# unonano.net
KiCad netlist of a schematic drawn in EAGLE
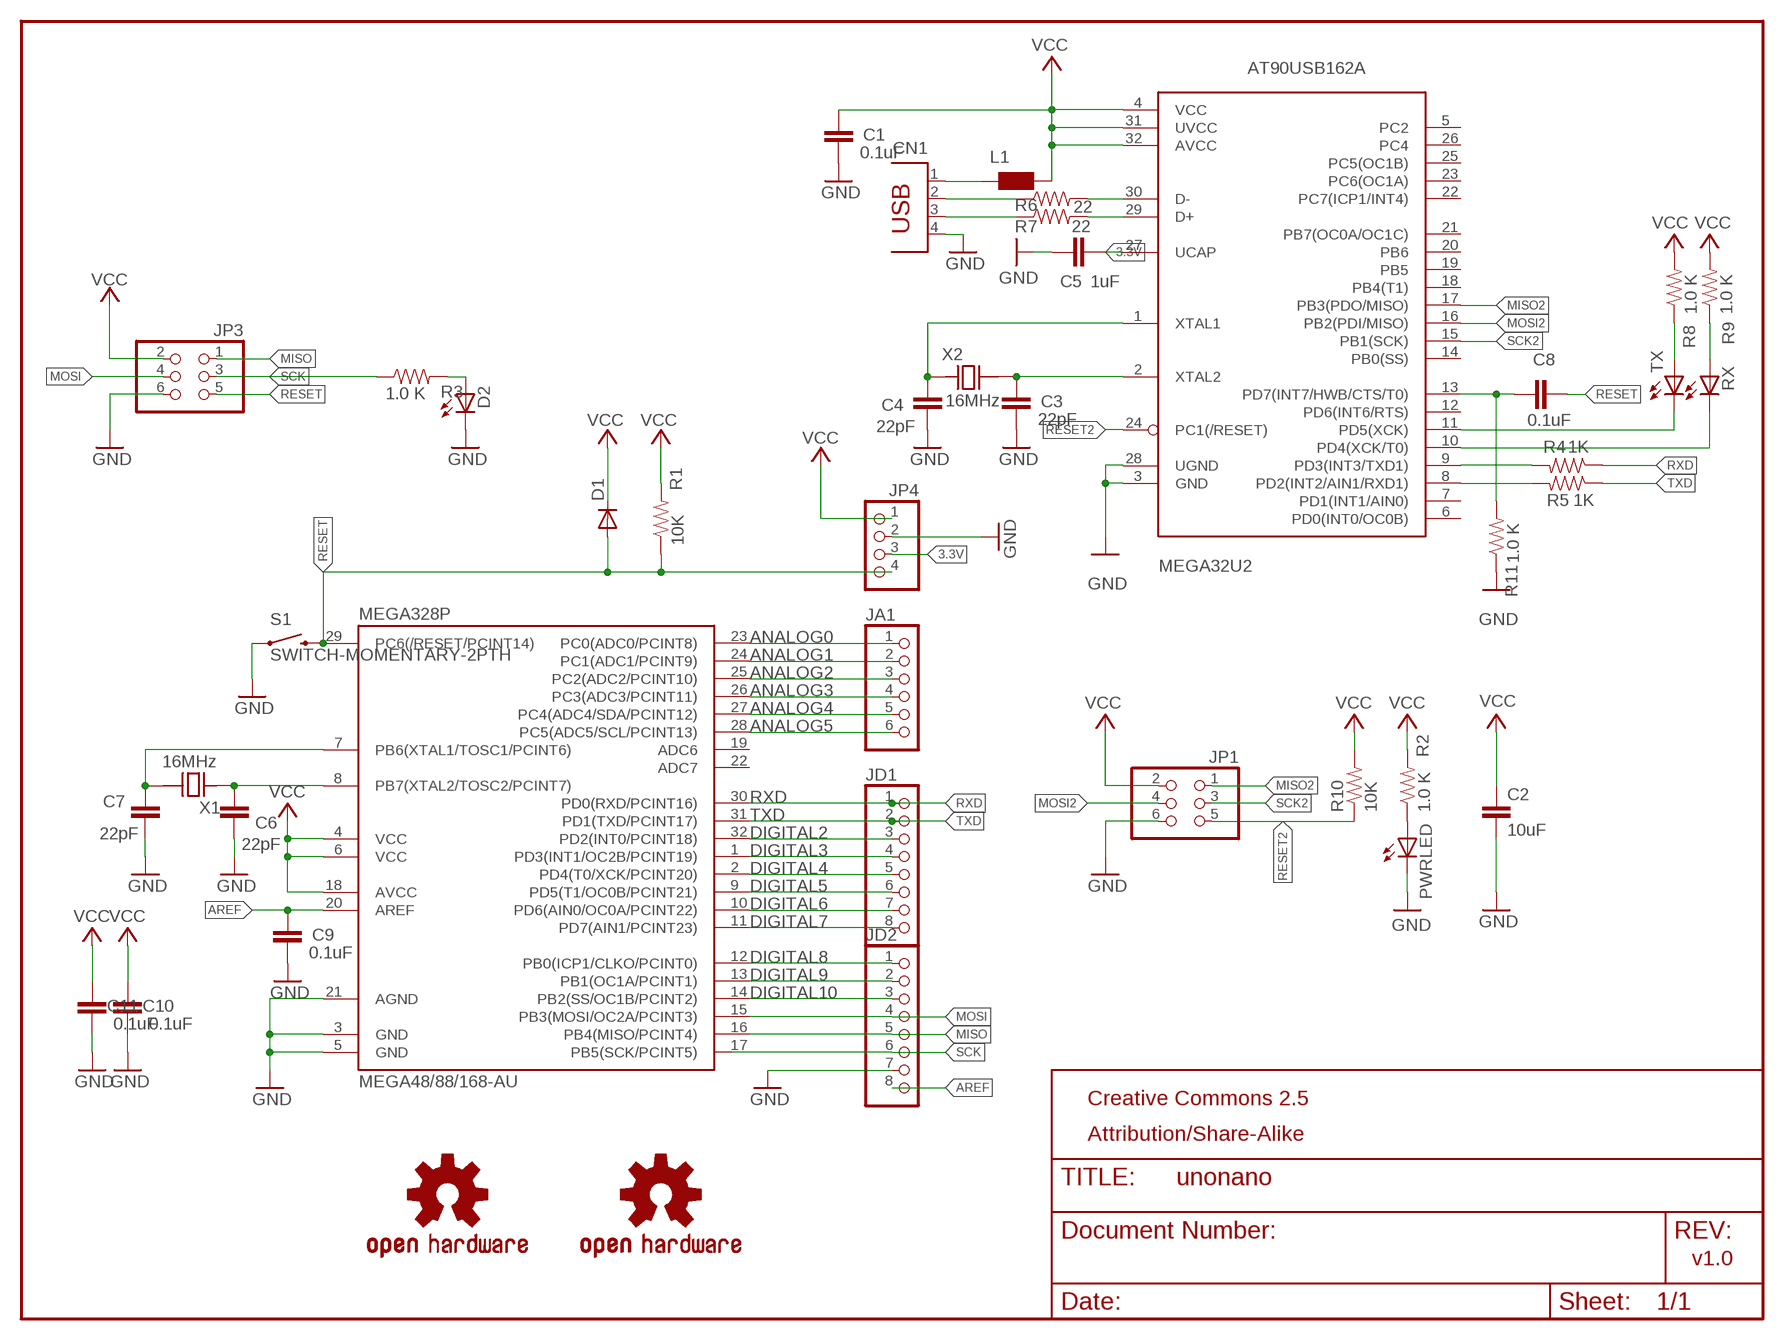
[diagram p0: schematic, sheet 1]

(export (version "E")
  (design (tool "Eeschema 10.0.6"))
  (components
    (comp (ref "C1")
      (value "0.1uF")
      (footprint "eagle-import:0805")
      (libsource (lib "eagle-import") (part "CAP0805"))
    )
    (comp (ref "C2")
      (value "10uF")
      (footprint "eagle-import:1206")
      (libsource (lib "eagle-import") (part "1.0UF50V10%(1206)"))
    )
    (comp (ref "C3")
      (value "22pF")
      (footprint "eagle-import:0805")
      (libsource (lib "eagle-import") (part "CAP0805"))
    )
    (comp (ref "C4")
      (value "22pF")
      (footprint "eagle-import:0805")
      (libsource (lib "eagle-import") (part "CAP0805"))
    )
    (comp (ref "C5")
      (value "1uF")
      (footprint "eagle-import:0805")
      (libsource (lib "eagle-import") (part "CAP0805"))
    )
    (comp (ref "C6")
      (value "22pF")
      (footprint "eagle-import:0805")
      (libsource (lib "eagle-import") (part "CAP0805"))
    )
    (comp (ref "C7")
      (value "22pF")
      (footprint "eagle-import:0805")
      (libsource (lib "eagle-import") (part "CAP0805"))
    )
    (comp (ref "C8")
      (value "0.1uF")
      (footprint "eagle-import:0805")
      (libsource (lib "eagle-import") (part "CAP0805"))
    )
    (comp (ref "C9")
      (value "0.1uF")
      (footprint "eagle-import:0805")
      (libsource (lib "eagle-import") (part "CAP0805"))
    )
    (comp (ref "C10")
      (value "0.1uF")
      (footprint "eagle-import:0805")
      (libsource (lib "eagle-import") (part "CAP0805"))
    )
    (comp (ref "C11")
      (value "0.1uF")
      (footprint "eagle-import:0805")
      (libsource (lib "eagle-import") (part "CAP0805"))
    )
    (comp (ref "CN1")
      (value "PN61729")
      (footprint "eagle-import:PN61729")
      (libsource (lib "eagle-import") (part "PN61729"))
    )
    (comp (ref "D1")
      (value "DIODESOD")
      (footprint "eagle-import:SOD-323")
      (libsource (lib "eagle-import") (part "DIODESOD"))
    )
    (comp (ref "D2")
      (value "Green")
      (footprint "eagle-import:CHIP-LED0805")
      (libsource (lib "eagle-import") (part "LEDCHIP-LED0805"))
    )
    (comp (ref "JA1")
      (value "PINHD-1X6CB")
      (footprint "eagle-import:1X06-CLEANBIG")
      (libsource (lib "eagle-import") (part "PINHD-1X6CB"))
    )
    (comp (ref "JD1")
      (value "PINHD-1X8CLEANBIG")
      (footprint "eagle-import:1X08-CLEANBIG")
      (libsource (lib "eagle-import") (part "PINHD-1X8CLEANBIG"))
    )
    (comp (ref "JD2")
      (value "PINHD-1X8CLEANBIG")
      (footprint "eagle-import:1X08-CLEANBIG")
      (libsource (lib "eagle-import") (part "PINHD-1X8CLEANBIG"))
    )
    (comp (ref "JP1")
      (value "PINHD-2X3")
      (footprint "eagle-import:2X03")
      (libsource (lib "eagle-import") (part "PINHD-2X3"))
    )
    (comp (ref "JP3")
      (value "PINHD-2X3")
      (footprint "eagle-import:2X03")
      (libsource (lib "eagle-import") (part "PINHD-2X3"))
    )
    (comp (ref "JP4")
      (value "PINHD-1X4CB")
      (footprint "eagle-import:1X04-CB")
      (libsource (lib "eagle-import") (part "PINHD-1X4CB"))
    )
    (comp (ref "L1")
      (value "WE-CBF")
      (footprint "eagle-import:1812")
      (libsource (lib "eagle-import") (part "WE-CBF"))
    )
    (comp (ref "LOGO1")
      (value "OSHW-LOGOL")
      (footprint "eagle-import:OSHW-LOGO-L")
      (libsource (lib "eagle-import") (part "OSHW-LOGOL"))
    )
    (comp (ref "LOGO2")
      (value "OSHW-LOGOS")
      (footprint "eagle-import:OSHW-LOGO-S")
      (libsource (lib "eagle-import") (part "OSHW-LOGOS"))
    )
    (comp (ref "MEGA32U2")
      (value "AT90USB162A")
      (footprint "eagle-import:TQFP32-08")
      (libsource (lib "eagle-import") (part "AT90USB162A"))
    )
    (comp (ref "MEGA328P")
      (value "MEGA48/88/168-AU")
      (footprint "eagle-import:TQFP32-08")
      (libsource (lib "eagle-import") (part "MEGA48/88/168-AU"))
    )
    (comp (ref "PWRLED")
      (value "LEDCHIP-LED0805")
      (footprint "eagle-import:CHIP-LED0805")
      (libsource (lib "eagle-import") (part "LEDCHIP-LED0805"))
    )
    (comp (ref "R1")
      (value "10K")
      (footprint "eagle-import:0805")
      (libsource (lib "eagle-import") (part "RESISTOR0805-RES"))
    )
    (comp (ref "R2")
      (value "1.0 K")
      (footprint "eagle-import:0805")
      (libsource (lib "eagle-import") (part "RESISTOR0805-RES"))
    )
    (comp (ref "R3")
      (value "1.0 K")
      (footprint "eagle-import:0805")
      (libsource (lib "eagle-import") (part "RESISTOR0805-RES"))
    )
    (comp (ref "R4")
      (value "1K")
      (footprint "eagle-import:0805")
      (libsource (lib "eagle-import") (part "RESISTOR0805-RES"))
    )
    (comp (ref "R5")
      (value "1K")
      (footprint "eagle-import:0805")
      (libsource (lib "eagle-import") (part "RESISTOR0805-RES"))
    )
    (comp (ref "R6")
      (value "22")
      (footprint "eagle-import:0805")
      (libsource (lib "eagle-import") (part "RESISTOR0805-RES"))
    )
    (comp (ref "R7")
      (value "22")
      (footprint "eagle-import:0805")
      (libsource (lib "eagle-import") (part "RESISTOR0805-RES"))
    )
    (comp (ref "R8")
      (value "1.0 K")
      (footprint "eagle-import:0805")
      (libsource (lib "eagle-import") (part "RESISTOR0805-RES"))
    )
    (comp (ref "R9")
      (value "1.0 K")
      (footprint "eagle-import:0805")
      (libsource (lib "eagle-import") (part "RESISTOR0805-RES"))
    )
    (comp (ref "R10")
      (value "10K")
      (footprint "eagle-import:0805")
      (libsource (lib "eagle-import") (part "RESISTOR0805-RES"))
    )
    (comp (ref "R11")
      (value "1.0 K")
      (footprint "eagle-import:0805")
      (libsource (lib "eagle-import") (part "RESISTOR0805-RES"))
    )
    (comp (ref "RX")
      (value "Green")
      (footprint "eagle-import:CHIP-LED0805")
      (libsource (lib "eagle-import") (part "LEDCHIP-LED0805"))
    )
    (comp (ref "S1")
      (value "SWITCH-MOMENTARY-2PTH")
      (footprint "eagle-import:TACTILE-PTH")
      (libsource (lib "eagle-import") (part "SWITCH-MOMENTARY-2PTH"))
    )
    (comp (ref "TX")
      (value "Green")
      (footprint "eagle-import:CHIP-LED0805")
      (libsource (lib "eagle-import") (part "LEDCHIP-LED0805"))
    )
    (comp (ref "X1")
      (value "16MHz")
      (footprint "eagle-import:FA238")
      (libsource (lib "eagle-import") (part "CRYSTALFA238"))
    )
    (comp (ref "X2")
      (value "16MHz")
      (footprint "eagle-import:FA238")
      (libsource (lib "eagle-import") (part "CRYSTALFA238"))
    )
  )
  (nets
    (net (code "1") (name "/ANALOG0") (class "Default")
      (node (ref "JA1") (pin "1") (pinfunction "1_1") (pintype "passive"))
      (node (ref "MEGA328P") (pin "23") (pinfunction "PC0(ADC0/PCINT8)_23") (pintype "bidirectional"))
    )
    (net (code "2") (name "/ANALOG1") (class "Default")
      (node (ref "JA1") (pin "2") (pinfunction "2_2") (pintype "passive"))
      (node (ref "MEGA328P") (pin "24") (pinfunction "PC1(ADC1/PCINT9)_24") (pintype "bidirectional"))
    )
    (net (code "3") (name "/ANALOG2") (class "Default")
      (node (ref "JA1") (pin "3") (pinfunction "3_3") (pintype "passive"))
      (node (ref "MEGA328P") (pin "25") (pinfunction "PC2(ADC2/PCINT10)_25") (pintype "bidirectional"))
    )
    (net (code "4") (name "/ANALOG3") (class "Default")
      (node (ref "JA1") (pin "4") (pinfunction "4_4") (pintype "passive"))
      (node (ref "MEGA328P") (pin "26") (pinfunction "PC3(ADC3/PCINT11)_26") (pintype "bidirectional"))
    )
    (net (code "5") (name "/ANALOG4") (class "Default")
      (node (ref "JA1") (pin "5") (pinfunction "5_5") (pintype "passive"))
      (node (ref "MEGA328P") (pin "27") (pinfunction "PC4(ADC4/SDA/PCINT12)_27") (pintype "bidirectional"))
    )
    (net (code "6") (name "/ANALOG5") (class "Default")
      (node (ref "JA1") (pin "6") (pinfunction "6_6") (pintype "passive"))
      (node (ref "MEGA328P") (pin "28") (pinfunction "PC5(ADC5/SCL/PCINT13)_28") (pintype "bidirectional"))
    )
    (net (code "7") (name "/DIGITAL2") (class "Default")
      (node (ref "JD1") (pin "3") (pinfunction "3_3") (pintype "passive"))
      (node (ref "MEGA328P") (pin "32") (pinfunction "PD2(INT0/PCINT18)_32") (pintype "bidirectional"))
    )
    (net (code "8") (name "/DIGITAL3") (class "Default")
      (node (ref "JD1") (pin "4") (pinfunction "4_4") (pintype "passive"))
      (node (ref "MEGA328P") (pin "1") (pinfunction "PD3(INT1/OC2B/PCINT19)_1") (pintype "bidirectional"))
    )
    (net (code "9") (name "/DIGITAL4") (class "Default")
      (node (ref "JD1") (pin "5") (pinfunction "5_5") (pintype "passive"))
      (node (ref "MEGA328P") (pin "2") (pinfunction "PD4(T0/XCK/PCINT20)_2") (pintype "bidirectional"))
    )
    (net (code "10") (name "/DIGITAL5") (class "Default")
      (node (ref "JD1") (pin "6") (pinfunction "6_6") (pintype "passive"))
      (node (ref "MEGA328P") (pin "9") (pinfunction "PD5(T1/OC0B/PCINT21)_9") (pintype "bidirectional"))
    )
    (net (code "11") (name "/DIGITAL6") (class "Default")
      (node (ref "JD1") (pin "7") (pinfunction "7_7") (pintype "passive"))
      (node (ref "MEGA328P") (pin "10") (pinfunction "PD6(AIN0/OC0A/PCINT22)_10") (pintype "bidirectional"))
    )
    (net (code "12") (name "/DIGITAL7") (class "Default")
      (node (ref "JD1") (pin "8") (pinfunction "8_8") (pintype "passive"))
      (node (ref "MEGA328P") (pin "11") (pinfunction "PD7(AIN1/PCINT23)_11") (pintype "bidirectional"))
    )
    (net (code "13") (name "/DIGITAL8") (class "Default")
      (node (ref "JD2") (pin "1") (pinfunction "1_1") (pintype "passive"))
      (node (ref "MEGA328P") (pin "12") (pinfunction "PB0(ICP1/CLKO/PCINT0)_12") (pintype "bidirectional"))
    )
    (net (code "14") (name "/DIGITAL9") (class "Default")
      (node (ref "JD2") (pin "2") (pinfunction "2_2") (pintype "passive"))
      (node (ref "MEGA328P") (pin "13") (pinfunction "PB1(OC1A/PCINT1)_13") (pintype "bidirectional"))
    )
    (net (code "15") (name "/DIGITAL10") (class "Default")
      (node (ref "JD2") (pin "3") (pinfunction "3_3") (pintype "passive"))
      (node (ref "MEGA328P") (pin "14") (pinfunction "PB2(SS/OC1B/PCINT2)_14") (pintype "bidirectional"))
    )
    (net (code "16") (name "3.3V") (class "Default")
      (node (ref "C5") (pin "1") (pinfunction "1_1") (pintype "passive"))
      (node (ref "JP4") (pin "3") (pinfunction "3_3") (pintype "passive"))
      (node (ref "MEGA32U2") (pin "27") (pinfunction "UCAP_27") (pintype "bidirectional"))
    )
    (net (code "17") (name "AREF") (class "Default")
      (node (ref "C9") (pin "1") (pinfunction "1_1") (pintype "passive"))
      (node (ref "JD2") (pin "8") (pinfunction "8_8") (pintype "passive"))
      (node (ref "MEGA328P") (pin "20") (pinfunction "AREF_20") (pintype "passive"))
    )
    (net (code "18") (name "GND") (class "Default")
      (node (ref "C1") (pin "2") (pinfunction "2_2") (pintype "passive"))
      (node (ref "C10") (pin "2") (pinfunction "2_2") (pintype "passive"))
      (node (ref "C11") (pin "2") (pinfunction "2_2") (pintype "passive"))
      (node (ref "C2") (pin "2") (pinfunction "2_2") (pintype "passive"))
      (node (ref "C3") (pin "2") (pinfunction "2_2") (pintype "passive"))
      (node (ref "C4") (pin "1") (pinfunction "1_1") (pintype "passive"))
      (node (ref "C5") (pin "2") (pinfunction "2_2") (pintype "passive"))
      (node (ref "C6") (pin "2") (pinfunction "2_2") (pintype "passive"))
      (node (ref "C7") (pin "1") (pinfunction "1_1") (pintype "passive"))
      (node (ref "C9") (pin "2") (pinfunction "2_2") (pintype "passive"))
      (node (ref "CN1") (pin "4") (pinfunction "4_4") (pintype "bidirectional"))
      (node (ref "D2") (pin "C") (pinfunction "C_C") (pintype "passive"))
      (node (ref "JD2") (pin "7") (pinfunction "7_7") (pintype "passive"))
      (node (ref "JP1") (pin "6") (pinfunction "6_6") (pintype "passive"))
      (node (ref "JP3") (pin "6") (pinfunction "6_6") (pintype "passive"))
      (node (ref "JP4") (pin "2") (pinfunction "2_2") (pintype "passive"))
      (node (ref "MEGA328P") (pin "21") (pinfunction "AGND_21") (pintype "power_in"))
      (node (ref "MEGA328P") (pin "3") (pinfunction "GND_3") (pintype "power_in"))
      (node (ref "MEGA328P") (pin "5") (pinfunction "GND_5") (pintype "power_in"))
      (node (ref "MEGA32U2") (pin "28") (pinfunction "UGND_28") (pintype "bidirectional"))
      (node (ref "MEGA32U2") (pin "3") (pinfunction "GND_3") (pintype "bidirectional"))
      (node (ref "PWRLED") (pin "C") (pinfunction "C_C") (pintype "passive"))
      (node (ref "R11") (pin "1") (pinfunction "1_1") (pintype "passive"))
      (node (ref "S1") (pin "1") (pinfunction "1_1") (pintype "passive"))
    )
    (net (code "19") (name "MISO") (class "Default")
      (node (ref "JD2") (pin "5") (pinfunction "5_5") (pintype "passive"))
      (node (ref "JP3") (pin "1") (pinfunction "1_1") (pintype "passive"))
      (node (ref "MEGA328P") (pin "16") (pinfunction "PB4(MISO/PCINT4)_16") (pintype "bidirectional"))
    )
    (net (code "20") (name "MISO2") (class "Default")
      (node (ref "JP1") (pin "1") (pinfunction "1_1") (pintype "passive"))
      (node (ref "MEGA32U2") (pin "17") (pinfunction "PB3(PDO/MISO)_17") (pintype "bidirectional"))
    )
    (net (code "21") (name "MOSI") (class "Default")
      (node (ref "JD2") (pin "4") (pinfunction "4_4") (pintype "passive"))
      (node (ref "JP3") (pin "4") (pinfunction "4_4") (pintype "passive"))
      (node (ref "MEGA328P") (pin "15") (pinfunction "PB3(MOSI/OC2A/PCINT3)_15") (pintype "bidirectional"))
    )
    (net (code "22") (name "MOSI2") (class "Default")
      (node (ref "JP1") (pin "4") (pinfunction "4_4") (pintype "passive"))
      (node (ref "MEGA32U2") (pin "16") (pinfunction "PB2(PDI/MISO)_16") (pintype "bidirectional"))
    )
    (net (code "23") (name "Net-(CN1-Pad1)") (class "Default")
      (node (ref "CN1") (pin "1") (pinfunction "1_1") (pintype "bidirectional"))
      (node (ref "L1") (pin "1") (pinfunction "1_1") (pintype "passive"))
    )
    (net (code "24") (name "Net-(CN1-Pad2)") (class "Default")
      (node (ref "CN1") (pin "2") (pinfunction "2_2") (pintype "bidirectional"))
      (node (ref "R6") (pin "1") (pinfunction "1_1") (pintype "passive"))
    )
    (net (code "25") (name "Net-(CN1-Pad3)") (class "Default")
      (node (ref "CN1") (pin "3") (pinfunction "3_3") (pintype "bidirectional"))
      (node (ref "R7") (pin "1") (pinfunction "1_1") (pintype "passive"))
    )
    (net (code "26") (name "Net-(D2-PadA)") (class "Default")
      (node (ref "D2") (pin "A") (pinfunction "A_A") (pintype "passive"))
      (node (ref "R3") (pin "2") (pinfunction "2_2") (pintype "passive"))
    )
    (net (code "27") (name "Net-(MEGA32U2-D+)") (class "Default")
      (node (ref "MEGA32U2") (pin "29") (pinfunction "D+_29") (pintype "bidirectional"))
      (node (ref "R7") (pin "2") (pinfunction "2_2") (pintype "passive"))
    )
    (net (code "28") (name "Net-(MEGA32U2-D-)") (class "Default")
      (node (ref "MEGA32U2") (pin "30") (pinfunction "D-_30") (pintype "bidirectional"))
      (node (ref "R6") (pin "2") (pinfunction "2_2") (pintype "passive"))
    )
    (net (code "29") (name "Net-(MEGA32U2-PD2(INT2{slash}AIN1{slash}RXD1))") (class "Default")
      (node (ref "MEGA32U2") (pin "8") (pinfunction "PD2(INT2/AIN1/RXD1)_8") (pintype "bidirectional"))
      (node (ref "R5") (pin "2") (pinfunction "2_2") (pintype "passive"))
    )
    (net (code "30") (name "Net-(MEGA32U2-PD3(INT3{slash}TXD1))") (class "Default")
      (node (ref "MEGA32U2") (pin "9") (pinfunction "PD3(INT3/TXD1)_9") (pintype "bidirectional"))
      (node (ref "R4") (pin "2") (pinfunction "2_2") (pintype "passive"))
    )
    (net (code "31") (name "Net-(MEGA32U2-PD4(XCK{slash}T0))") (class "Default")
      (node (ref "MEGA32U2") (pin "10") (pinfunction "PD4(XCK/T0)_10") (pintype "bidirectional"))
      (node (ref "RX") (pin "C") (pinfunction "C_C") (pintype "passive"))
    )
    (net (code "32") (name "Net-(MEGA32U2-PD5(XCK))") (class "Default")
      (node (ref "MEGA32U2") (pin "11") (pinfunction "PD5(XCK)_11") (pintype "bidirectional"))
      (node (ref "TX") (pin "C") (pinfunction "C_C") (pintype "passive"))
    )
    (net (code "33") (name "Net-(MEGA32U2-PD7(INT7{slash}HWB{slash}CTS{slash}T0))") (class "Default")
      (node (ref "C8") (pin "1") (pinfunction "1_1") (pintype "passive"))
      (node (ref "MEGA32U2") (pin "13") (pinfunction "PD7(INT7/HWB/CTS/T0)_13") (pintype "bidirectional"))
      (node (ref "R11") (pin "2") (pinfunction "2_2") (pintype "passive"))
    )
    (net (code "34") (name "Net-(MEGA32U2-XTAL1)") (class "Default")
      (node (ref "C4") (pin "2") (pinfunction "2_2") (pintype "passive"))
      (node (ref "MEGA32U2") (pin "1") (pinfunction "XTAL1_1") (pintype "bidirectional"))
      (node (ref "X2") (pin "1") (pinfunction "0_1") (pintype "passive"))
    )
    (net (code "35") (name "Net-(MEGA32U2-XTAL2)") (class "Default")
      (node (ref "C3") (pin "1") (pinfunction "1_1") (pintype "passive"))
      (node (ref "MEGA32U2") (pin "2") (pinfunction "XTAL2_2") (pintype "bidirectional"))
      (node (ref "X2") (pin "3") (pinfunction "1_3") (pintype "passive"))
    )
    (net (code "36") (name "Net-(MEGA328P-PB6(XTAL1{slash}TOSC1{slash}PCINT6))") (class "Default")
      (node (ref "C7") (pin "2") (pinfunction "2_2") (pintype "passive"))
      (node (ref "MEGA328P") (pin "7") (pinfunction "PB6(XTAL1/TOSC1/PCINT6)_7") (pintype "bidirectional"))
      (node (ref "X1") (pin "3") (pinfunction "1_3") (pintype "passive"))
    )
    (net (code "37") (name "Net-(MEGA328P-PB7(XTAL2{slash}TOSC2{slash}PCINT7))") (class "Default")
      (node (ref "C6") (pin "1") (pinfunction "1_1") (pintype "passive"))
      (node (ref "MEGA328P") (pin "8") (pinfunction "PB7(XTAL2/TOSC2/PCINT7)_8") (pintype "bidirectional"))
      (node (ref "X1") (pin "1") (pinfunction "0_1") (pintype "passive"))
    )
    (net (code "38") (name "Net-(PWRLED-PadA)") (class "Default")
      (node (ref "PWRLED") (pin "A") (pinfunction "A_A") (pintype "passive"))
      (node (ref "R2") (pin "1") (pinfunction "1_1") (pintype "passive"))
    )
    (net (code "39") (name "Net-(R8-Pad1)") (class "Default")
      (node (ref "R8") (pin "1") (pinfunction "1_1") (pintype "passive"))
      (node (ref "TX") (pin "A") (pinfunction "A_A") (pintype "passive"))
    )
    (net (code "40") (name "Net-(R9-Pad1)") (class "Default")
      (node (ref "R9") (pin "1") (pinfunction "1_1") (pintype "passive"))
      (node (ref "RX") (pin "A") (pinfunction "A_A") (pintype "passive"))
    )
    (net (code "41") (name "RESET") (class "Default")
      (node (ref "C8") (pin "2") (pinfunction "2_2") (pintype "passive"))
      (node (ref "D1") (pin "2") (pinfunction "A_2") (pintype "passive"))
      (node (ref "JP3") (pin "5") (pinfunction "5_5") (pintype "passive"))
      (node (ref "JP4") (pin "4") (pinfunction "4_4") (pintype "passive"))
      (node (ref "MEGA328P") (pin "29") (pinfunction "PC6(/RESET/PCINT14)_29") (pintype "bidirectional"))
      (node (ref "R1") (pin "1") (pinfunction "1_1") (pintype "passive"))
      (node (ref "S1") (pin "3") (pinfunction "2_3") (pintype "passive"))
    )
    (net (code "42") (name "RESET2") (class "Default")
      (node (ref "JP1") (pin "5") (pinfunction "5_5") (pintype "passive"))
      (node (ref "MEGA32U2") (pin "24") (pinfunction "PC1(/RESET)_24") (pintype "bidirectional"))
      (node (ref "R10") (pin "1") (pinfunction "1_1") (pintype "passive"))
    )
    (net (code "43") (name "RXD") (class "Default")
      (node (ref "JD1") (pin "1") (pinfunction "1_1") (pintype "passive"))
      (node (ref "MEGA328P") (pin "30") (pinfunction "PD0(RXD/PCINT16)_30") (pintype "bidirectional"))
      (node (ref "R4") (pin "1") (pinfunction "1_1") (pintype "passive"))
    )
    (net (code "44") (name "SCK") (class "Default")
      (node (ref "JD2") (pin "6") (pinfunction "6_6") (pintype "passive"))
      (node (ref "JP3") (pin "3") (pinfunction "3_3") (pintype "passive"))
      (node (ref "MEGA328P") (pin "17") (pinfunction "PB5(SCK/PCINT5)_17") (pintype "bidirectional"))
      (node (ref "R3") (pin "1") (pinfunction "1_1") (pintype "passive"))
    )
    (net (code "45") (name "SCK2") (class "Default")
      (node (ref "JP1") (pin "3") (pinfunction "3_3") (pintype "passive"))
      (node (ref "MEGA32U2") (pin "15") (pinfunction "PB1(SCK)_15") (pintype "bidirectional"))
    )
    (net (code "46") (name "TXD") (class "Default")
      (node (ref "JD1") (pin "2") (pinfunction "2_2") (pintype "passive"))
      (node (ref "MEGA328P") (pin "31") (pinfunction "PD1(TXD/PCINT17)_31") (pintype "bidirectional"))
      (node (ref "R5") (pin "1") (pinfunction "1_1") (pintype "passive"))
    )
    (net (code "47") (name "VCC") (class "Default")
      (node (ref "C1") (pin "1") (pinfunction "1_1") (pintype "passive"))
      (node (ref "C10") (pin "1") (pinfunction "1_1") (pintype "passive"))
      (node (ref "C11") (pin "1") (pinfunction "1_1") (pintype "passive"))
      (node (ref "C2") (pin "1") (pinfunction "1_1") (pintype "passive"))
      (node (ref "D1") (pin "1") (pinfunction "C_1") (pintype "passive"))
      (node (ref "JP1") (pin "2") (pinfunction "2_2") (pintype "passive"))
      (node (ref "JP3") (pin "2") (pinfunction "2_2") (pintype "passive"))
      (node (ref "JP4") (pin "1") (pinfunction "1_1") (pintype "passive"))
      (node (ref "L1") (pin "2") (pinfunction "2_2") (pintype "passive"))
      (node (ref "MEGA328P") (pin "18") (pinfunction "AVCC_18") (pintype "passive"))
      (node (ref "MEGA328P") (pin "4") (pinfunction "VCC_4") (pintype "power_in"))
      (node (ref "MEGA328P") (pin "6") (pinfunction "VCC_6") (pintype "power_in"))
      (node (ref "MEGA32U2") (pin "31") (pinfunction "UVCC_31") (pintype "bidirectional"))
      (node (ref "MEGA32U2") (pin "32") (pinfunction "AVCC_32") (pintype "bidirectional"))
      (node (ref "MEGA32U2") (pin "4") (pinfunction "VCC_4") (pintype "bidirectional"))
      (node (ref "R1") (pin "2") (pinfunction "2_2") (pintype "passive"))
      (node (ref "R10") (pin "2") (pinfunction "2_2") (pintype "passive"))
      (node (ref "R2") (pin "2") (pinfunction "2_2") (pintype "passive"))
      (node (ref "R8") (pin "2") (pinfunction "2_2") (pintype "passive"))
      (node (ref "R9") (pin "2") (pinfunction "2_2") (pintype "passive"))
    )
    (net (code "48") (name "unconnected-(MEGA32U2-PB0(SS)-Pad14)") (class "Default")
      (node (ref "MEGA32U2") (pin "14") (pinfunction "PB0(SS)_14") (pintype "bidirectional"))
    )
    (net (code "49") (name "unconnected-(MEGA32U2-PB4(T1)-Pad18)") (class "Default")
      (node (ref "MEGA32U2") (pin "18") (pinfunction "PB4(T1)_18") (pintype "bidirectional"))
    )
    (net (code "50") (name "unconnected-(MEGA32U2-PB5-Pad19)") (class "Default")
      (node (ref "MEGA32U2") (pin "19") (pinfunction "PB5_19") (pintype "bidirectional"))
    )
    (net (code "51") (name "unconnected-(MEGA32U2-PB6-Pad20)") (class "Default")
      (node (ref "MEGA32U2") (pin "20") (pinfunction "PB6_20") (pintype "bidirectional"))
    )
    (net (code "52") (name "unconnected-(MEGA32U2-PB7(OC0A{slash}OC1C)-Pad21)") (class "Default")
      (node (ref "MEGA32U2") (pin "21") (pinfunction "PB7(OC0A/OC1C)_21") (pintype "bidirectional"))
    )
    (net (code "53") (name "unconnected-(MEGA32U2-PC2-Pad5)") (class "Default")
      (node (ref "MEGA32U2") (pin "5") (pinfunction "PC2_5") (pintype "bidirectional"))
    )
    (net (code "54") (name "unconnected-(MEGA32U2-PC4-Pad26)") (class "Default")
      (node (ref "MEGA32U2") (pin "26") (pinfunction "PC4_26") (pintype "bidirectional"))
    )
    (net (code "55") (name "unconnected-(MEGA32U2-PC5(OC1B)-Pad25)") (class "Default")
      (node (ref "MEGA32U2") (pin "25") (pinfunction "PC5(OC1B)_25") (pintype "bidirectional"))
    )
    (net (code "56") (name "unconnected-(MEGA32U2-PC6(OC1A)-Pad23)") (class "Default")
      (node (ref "MEGA32U2") (pin "23") (pinfunction "PC6(OC1A)_23") (pintype "bidirectional"))
    )
    (net (code "57") (name "unconnected-(MEGA32U2-PC7(ICP1{slash}INT4)-Pad22)") (class "Default")
      (node (ref "MEGA32U2") (pin "22") (pinfunction "PC7(ICP1/INT4)_22") (pintype "bidirectional"))
    )
    (net (code "58") (name "unconnected-(MEGA32U2-PD0(INT0{slash}OC0B)-Pad6)") (class "Default")
      (node (ref "MEGA32U2") (pin "6") (pinfunction "PD0(INT0/OC0B)_6") (pintype "bidirectional"))
    )
    (net (code "59") (name "unconnected-(MEGA32U2-PD1(INT1{slash}AIN0)-Pad7)") (class "Default")
      (node (ref "MEGA32U2") (pin "7") (pinfunction "PD1(INT1/AIN0)_7") (pintype "bidirectional"))
    )
    (net (code "60") (name "unconnected-(MEGA32U2-PD6(INT6{slash}RTS)-Pad12)") (class "Default")
      (node (ref "MEGA32U2") (pin "12") (pinfunction "PD6(INT6/RTS)_12") (pintype "bidirectional"))
    )
    (net (code "61") (name "unconnected-(MEGA328P-ADC6-Pad19)") (class "Default")
      (node (ref "MEGA328P") (pin "19") (pinfunction "ADC6_19") (pintype "passive"))
    )
    (net (code "62") (name "unconnected-(MEGA328P-ADC7-Pad22)") (class "Default")
      (node (ref "MEGA328P") (pin "22") (pinfunction "ADC7_22") (pintype "passive"))
    )
  )
)
